# Haar.net
KiCad netlist of a schematic drawn in EAGLE
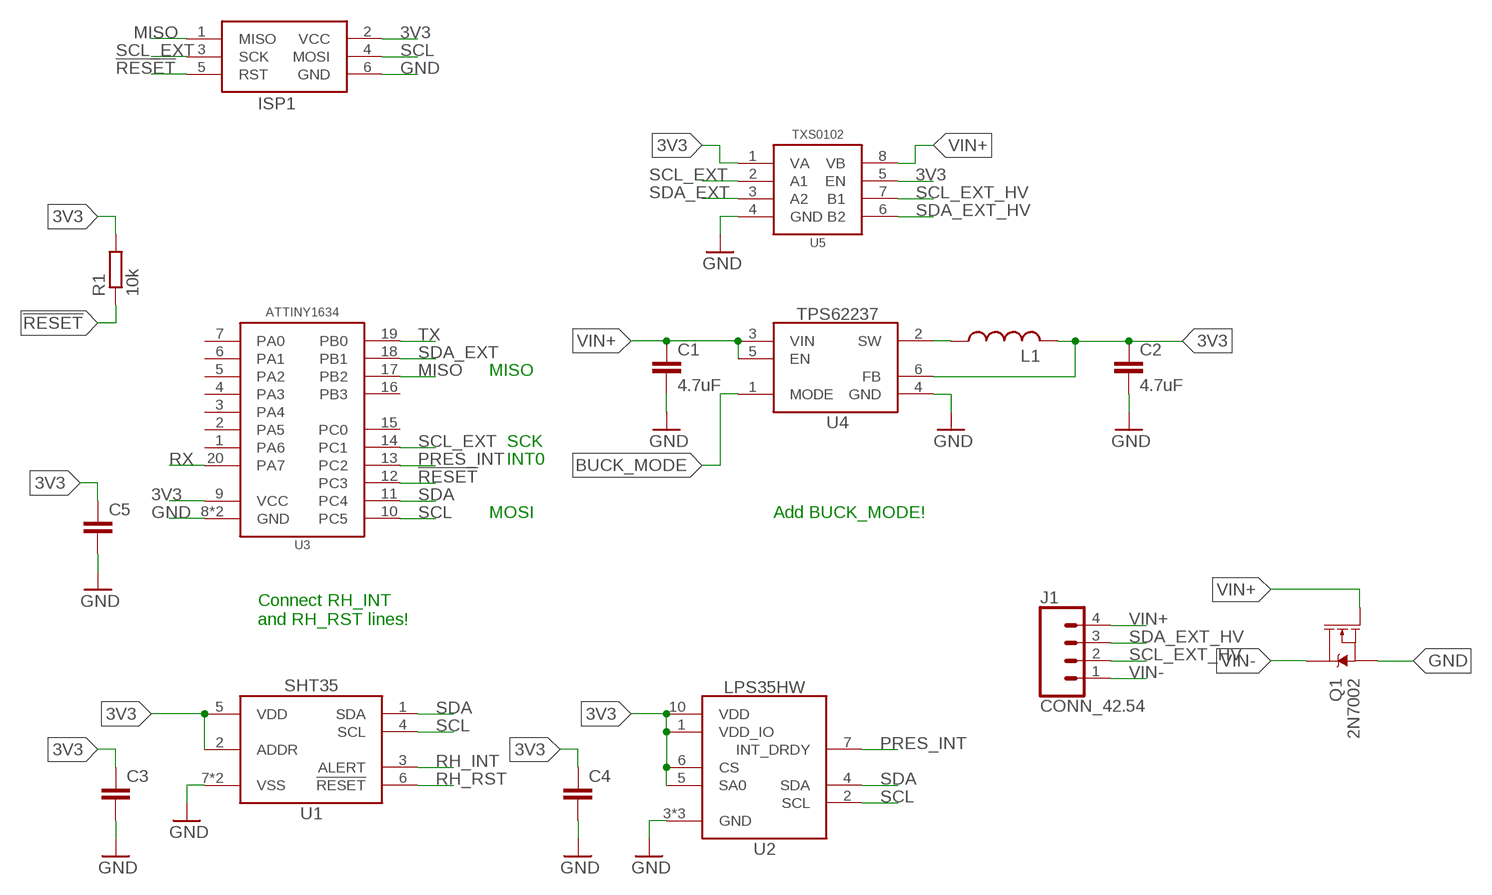
[diagram p0: schematic, sheet 1]

(export (version "E")
  (design (tool "Eeschema 10.0.6"))
  (components
    (comp (ref "C1")
      (value "4.7uF")
      (footprint "eagle-import:C0402")
      (libsource (lib "eagle-import") (part "C-EUC0402"))
    )
    (comp (ref "C2")
      (value "4.7uF")
      (footprint "eagle-import:C0402")
      (libsource (lib "eagle-import") (part "C-EUC0402"))
    )
    (comp (ref "C3")
      (value "C-EU0.1UFC0402")
      (footprint "eagle-import:C0402")
      (fields (field (name "MF") "Murata") (field (name "MPN") "GCM155R71C104KA55D"))
      (libsource (lib "eagle-import") (part "C-EUC04020.1UF"))
    )
    (comp (ref "C4")
      (value "C-EU0.1UFC0402")
      (footprint "eagle-import:C0402")
      (fields (field (name "MF") "Murata") (field (name "MPN") "GCM155R71C104KA55D"))
      (libsource (lib "eagle-import") (part "C-EUC04020.1UF"))
    )
    (comp (ref "C5")
      (value "C-EU0.1UFC0402")
      (footprint "eagle-import:C0402")
      (fields (field (name "MF") "Murata") (field (name "MPN") "GCM155R71C104KA55D"))
      (libsource (lib "eagle-import") (part "C-EUC04020.1UF"))
    )
    (comp (ref "ISP1")
      (value "AVRISP1.27MM")
      (footprint "eagle-import:2X3_1.27")
      (libsource (lib "eagle-import") (part "AVRISP1.27MM"))
    )
    (comp (ref "J1")
      (value "CONN_42.54")
      (footprint "eagle-import:1X04")
      (libsource (lib "eagle-import") (part "CONN_42.54"))
    )
    (comp (ref "L1")
      (value "INDUCTOR0805")
      (footprint "eagle-import:0805")
      (libsource (lib "eagle-import") (part "INDUCTOR0805"))
    )
    (comp (ref "Q1")
      (value "2N7002")
      (footprint "eagle-import:SOT323")
      (fields (field (name "MF") "Diodes Incorporated") (field (name "MPN") "2N7002W-7-F"))
      (libsource (lib "eagle-import") (part "MOSFET-NCH-2N7002PW"))
    )
    (comp (ref "R1")
      (value "10k")
      (footprint "eagle-import:R0402")
      (fields (field (name "MF") "Yageo") (field (name "MPN") "RC0402JR-0710KL"))
      (libsource (lib "eagle-import") (part "R-EU_R040210K"))
    )
    (comp (ref "U1")
      (value "SHT35DFN")
      (footprint "eagle-import:DFN_8_2.5X2.5")
      (fields
        (field (name "DISP") "SHT35")
        (field (name "MF") "Sensirion")
        (field (name "MPN") "SHT35-DIS-F2.5KS")
      )
      (libsource (lib "eagle-import") (part "SHT3DFN5"))
    )
    (comp (ref "U2")
      (value "LPS35HW")
      (footprint "eagle-import:CCLGA10L")
      (fields (field (name "DISP") "LPS35HW") (field (name "MF") "ST") (field (name "MPN") "LPS35HWTR"))
      (libsource (lib "eagle-import") (part "LPS3HW5"))
    )
    (comp (ref "U3")
      (value "ATTINY1634QFN")
      (footprint "eagle-import:QFN20")
      (fields (field (name "MF") "Atmel") (field (name "MPN") "ATTINY1634-MUR"))
      (libsource (lib "eagle-import") (part "ATTINY1634QFN"))
    )
    (comp (ref "U4")
      (value "TPS62237DRY")
      (footprint "eagle-import:DRY0006A")
      (fields (field (name "DISP") "TPS62237") (field (name "MF") "TI") (field (name "MPN") "TPS62237DRYR"))
      (libsource (lib "eagle-import") (part "TPS6223DRY7"))
    )
    (comp (ref "U5")
      (value "TXS0102DQM")
      (footprint "eagle-import:DQM_R-PX2SON-N8")
      (fields (field (name "MF") "TI") (field (name "MPN") "TXS0102DQMR"))
      (libsource (lib "eagle-import") (part "TXS0102DQM"))
    )
  )
  (nets
    (net (code "1") (name "/MISO") (class "Default")
      (node (ref "ISP1") (pin "1") (pinfunction "MISO_1") (pintype "input"))
      (node (ref "U3") (pin "17") (pinfunction "PB2_17") (pintype "bidirectional"))
    )
    (net (code "2") (name "/PRES_INT") (class "Default")
      (node (ref "U2") (pin "7") (pinfunction "INT_DRDY_7") (pintype "output"))
      (node (ref "U3") (pin "13") (pinfunction "PC2_13") (pintype "bidirectional"))
    )
    (net (code "3") (name "/RH_INT") (class "Default")
      (node (ref "U1") (pin "3") (pinfunction "ALERT_3") (pintype "output"))
    )
    (net (code "4") (name "/RH_RST") (class "Default")
      (node (ref "U1") (pin "6") (pinfunction "~{RESET}_6") (pintype "input"))
    )
    (net (code "5") (name "/RX") (class "Default")
      (node (ref "U3") (pin "20") (pinfunction "PA7_20") (pintype "bidirectional"))
    )
    (net (code "6") (name "/SCL") (class "Default")
      (node (ref "ISP1") (pin "4") (pinfunction "MOSI_4") (pintype "output"))
      (node (ref "U1") (pin "4") (pinfunction "SCL_4") (pintype "input"))
      (node (ref "U2") (pin "2") (pinfunction "SCL_2") (pintype "input"))
      (node (ref "U3") (pin "10") (pinfunction "PC5_10") (pintype "bidirectional"))
    )
    (net (code "7") (name "/SCL_EXT") (class "Default")
      (node (ref "ISP1") (pin "3") (pinfunction "SCK_3") (pintype "output"))
      (node (ref "U3") (pin "14") (pinfunction "PC1_14") (pintype "bidirectional"))
      (node (ref "U5") (pin "2") (pinfunction "A1_2") (pintype "bidirectional"))
    )
    (net (code "8") (name "/SCL_EXT_HV") (class "Default")
      (node (ref "J1") (pin "2") (pinfunction "2_2") (pintype "passive"))
      (node (ref "U5") (pin "7") (pinfunction "B1_7") (pintype "bidirectional"))
    )
    (net (code "9") (name "/SDA") (class "Default")
      (node (ref "U1") (pin "1") (pinfunction "SDA_1") (pintype "bidirectional"))
      (node (ref "U2") (pin "4") (pinfunction "SDA_4") (pintype "bidirectional"))
      (node (ref "U3") (pin "11") (pinfunction "PC4_11") (pintype "bidirectional"))
    )
    (net (code "10") (name "/SDA_EXT") (class "Default")
      (node (ref "U3") (pin "18") (pinfunction "PB1_18") (pintype "bidirectional"))
      (node (ref "U5") (pin "3") (pinfunction "A2_3") (pintype "bidirectional"))
    )
    (net (code "11") (name "/SDA_EXT_HV") (class "Default")
      (node (ref "J1") (pin "3") (pinfunction "3_3") (pintype "passive"))
      (node (ref "U5") (pin "6") (pinfunction "B2_6") (pintype "bidirectional"))
    )
    (net (code "12") (name "/TX") (class "Default")
      (node (ref "U3") (pin "19") (pinfunction "PB0_19") (pintype "bidirectional"))
    )
    (net (code "13") (name "/~{RESET}") (class "Default")
      (node (ref "ISP1") (pin "5") (pinfunction "RST_5") (pintype "output"))
      (node (ref "R1") (pin "1") (pinfunction "1_1") (pintype "passive"))
      (node (ref "U3") (pin "12") (pinfunction "PC3_12") (pintype "bidirectional"))
    )
    (net (code "14") (name "3V3") (class "Default")
      (node (ref "C2") (pin "1") (pinfunction "1_1") (pintype "passive"))
      (node (ref "C3") (pin "1") (pinfunction "1_1") (pintype "passive"))
      (node (ref "C4") (pin "1") (pinfunction "1_1") (pintype "passive"))
      (node (ref "C5") (pin "1") (pinfunction "1_1") (pintype "passive"))
      (node (ref "ISP1") (pin "2") (pinfunction "VCC_2") (pintype "power_in"))
      (node (ref "L1") (pin "2") (pinfunction "2_2") (pintype "passive"))
      (node (ref "R1") (pin "2") (pinfunction "2_2") (pintype "passive"))
      (node (ref "U1") (pin "2") (pinfunction "ADDR_2") (pintype "input"))
      (node (ref "U1") (pin "5") (pinfunction "VDD_5") (pintype "power_in"))
      (node (ref "U2") (pin "1") (pinfunction "VDD_IO_1") (pintype "power_in"))
      (node (ref "U2") (pin "10") (pinfunction "VDD_10") (pintype "power_in"))
      (node (ref "U2") (pin "5") (pinfunction "SA0_5") (pintype "input"))
      (node (ref "U2") (pin "6") (pinfunction "CS_6") (pintype "input"))
      (node (ref "U3") (pin "9") (pinfunction "VCC_9") (pintype "power_in"))
      (node (ref "U4") (pin "6") (pinfunction "FB_6") (pintype "input"))
      (node (ref "U5") (pin "1") (pinfunction "VA_1") (pintype "power_in"))
      (node (ref "U5") (pin "5") (pinfunction "EN_5") (pintype "input"))
    )
    (net (code "15") (name "BUCK_MODE") (class "Default")
      (node (ref "U4") (pin "1") (pinfunction "MODE_1") (pintype "input"))
    )
    (net (code "16") (name "GND") (class "Default")
      (node (ref "C1") (pin "2") (pinfunction "2_2") (pintype "passive"))
      (node (ref "C2") (pin "2") (pinfunction "2_2") (pintype "passive"))
      (node (ref "C3") (pin "2") (pinfunction "2_2") (pintype "passive"))
      (node (ref "C4") (pin "2") (pinfunction "2_2") (pintype "passive"))
      (node (ref "C5") (pin "2") (pinfunction "2_2") (pintype "passive"))
      (node (ref "ISP1") (pin "6") (pinfunction "GND_6") (pintype "power_in"))
      (node (ref "Q1") (pin "2") (pinfunction "S_2") (pintype "bidirectional"))
      (node (ref "U1") (pin "7") (pinfunction "VSS_7") (pintype "power_in"))
      (node (ref "U1") (pin "8") (pinfunction "VSS_8") (pintype "power_in"))
      (node (ref "U2") (pin "3") (pinfunction "GND_3") (pintype "power_in"))
      (node (ref "U2") (pin "8") (pinfunction "GND_8") (pintype "power_in"))
      (node (ref "U2") (pin "9") (pinfunction "GND_9") (pintype "power_in"))
      (node (ref "U3") (pin "8") (pinfunction "GND_8") (pintype "power_in"))
      (node (ref "U3") (pin "EP") (pinfunction "GND_EP") (pintype "power_in"))
      (node (ref "U4") (pin "4") (pinfunction "GND_4") (pintype "power_in"))
      (node (ref "U5") (pin "4") (pinfunction "GND_4") (pintype "power_in"))
    )
    (net (code "17") (name "Net-(U4-SW)") (class "Default")
      (node (ref "L1") (pin "1") (pinfunction "1_1") (pintype "passive"))
      (node (ref "U4") (pin "2") (pinfunction "SW_2") (pintype "output"))
    )
    (net (code "18") (name "VIN+") (class "Default")
      (node (ref "C1") (pin "1") (pinfunction "1_1") (pintype "passive"))
      (node (ref "J1") (pin "4") (pinfunction "4_4") (pintype "passive"))
      (node (ref "Q1") (pin "1") (pinfunction "G_1") (pintype "bidirectional"))
      (node (ref "U4") (pin "3") (pinfunction "VIN_3") (pintype "power_in"))
      (node (ref "U4") (pin "5") (pinfunction "EN_5") (pintype "input"))
      (node (ref "U5") (pin "8") (pinfunction "VB_8") (pintype "power_in"))
    )
    (net (code "19") (name "VIN-") (class "Default")
      (node (ref "J1") (pin "1") (pinfunction "1_1") (pintype "passive"))
      (node (ref "Q1") (pin "3") (pinfunction "D_3") (pintype "bidirectional"))
    )
    (net (code "20") (name "unconnected-(U3-PA0-Pad7)") (class "Default")
      (node (ref "U3") (pin "7") (pinfunction "PA0_7") (pintype "bidirectional"))
    )
    (net (code "21") (name "unconnected-(U3-PA1-Pad6)") (class "Default")
      (node (ref "U3") (pin "6") (pinfunction "PA1_6") (pintype "bidirectional"))
    )
    (net (code "22") (name "unconnected-(U3-PA2-Pad5)") (class "Default")
      (node (ref "U3") (pin "5") (pinfunction "PA2_5") (pintype "bidirectional"))
    )
    (net (code "23") (name "unconnected-(U3-PA3-Pad4)") (class "Default")
      (node (ref "U3") (pin "4") (pinfunction "PA3_4") (pintype "bidirectional"))
    )
    (net (code "24") (name "unconnected-(U3-PA4-Pad3)") (class "Default")
      (node (ref "U3") (pin "3") (pinfunction "PA4_3") (pintype "bidirectional"))
    )
    (net (code "25") (name "unconnected-(U3-PA5-Pad2)") (class "Default")
      (node (ref "U3") (pin "2") (pinfunction "PA5_2") (pintype "bidirectional"))
    )
    (net (code "26") (name "unconnected-(U3-PA6-Pad1)") (class "Default")
      (node (ref "U3") (pin "1") (pinfunction "PA6_1") (pintype "bidirectional"))
    )
    (net (code "27") (name "unconnected-(U3-PB3-Pad16)") (class "Default")
      (node (ref "U3") (pin "16") (pinfunction "PB3_16") (pintype "bidirectional"))
    )
    (net (code "28") (name "unconnected-(U3-PC0-Pad15)") (class "Default")
      (node (ref "U3") (pin "15") (pinfunction "PC0_15") (pintype "bidirectional"))
    )
  )
)
